# DUE_shield.net
KiCad netlist of a schematic drawn in EAGLE
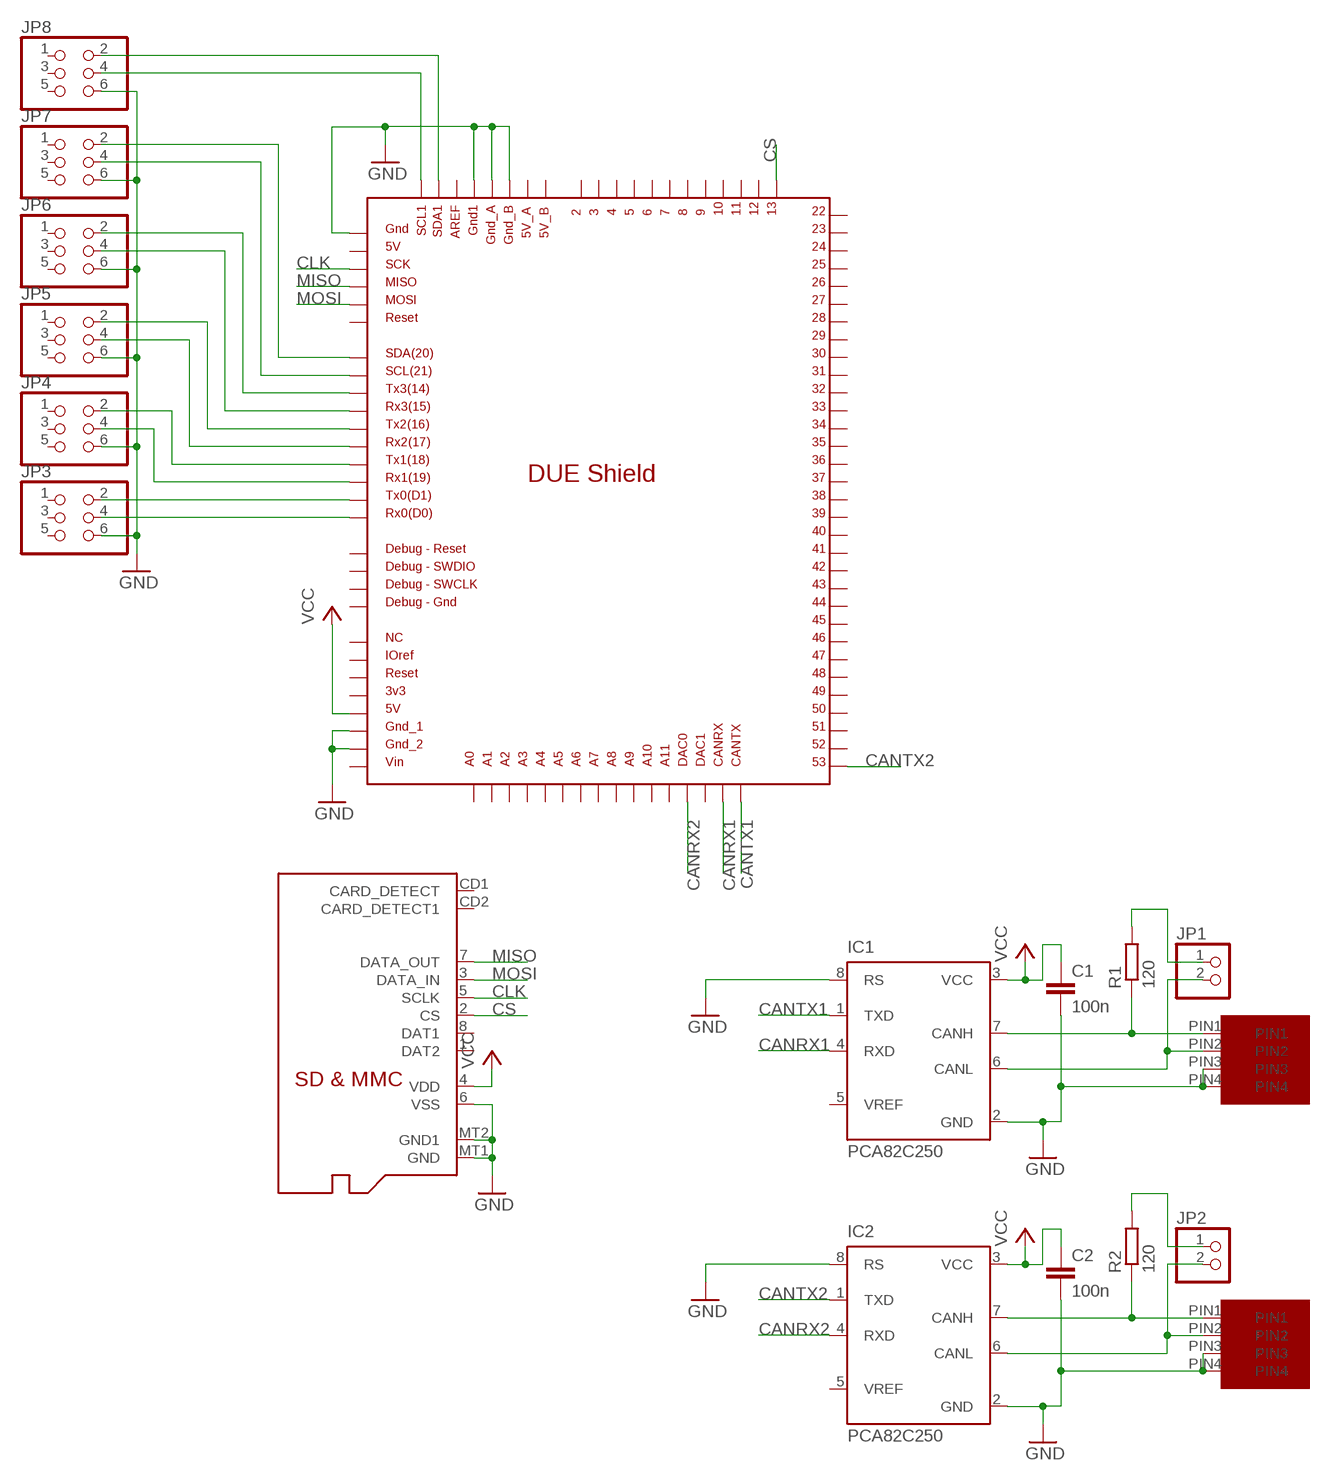
[diagram p0: schematic, sheet 1]

(export (version "E")
  (design (tool "Eeschema 10.0.6"))
  (components
    (comp (ref "C1")
      (value "100n")
      (footprint "eagle-import:C050-024X044")
      (libsource (lib "eagle-import") (part "C-EU050-024X044"))
    )
    (comp (ref "C2")
      (value "100n")
      (footprint "eagle-import:C050-024X044")
      (libsource (lib "eagle-import") (part "C-EU050-024X044"))
    )
    (comp (ref "IC1")
      (value "PCA82C250")
      (footprint "eagle-import:DIL08")
      (libsource (lib "eagle-import") (part "PCA82C250"))
    )
    (comp (ref "IC2")
      (value "PCA82C250")
      (footprint "eagle-import:DIL08")
      (libsource (lib "eagle-import") (part "PCA82C250"))
    )
    (comp (ref "JP1")
      (value "PINHD-1X2")
      (footprint "eagle-import:1X02")
      (libsource (lib "eagle-import") (part "PINHD-1X2"))
    )
    (comp (ref "JP2")
      (value "PINHD-1X2")
      (footprint "eagle-import:1X02")
      (libsource (lib "eagle-import") (part "PINHD-1X2"))
    )
    (comp (ref "JP3")
      (value "PINHD-2X3")
      (footprint "eagle-import:2X03")
      (libsource (lib "eagle-import") (part "PINHD-2X3"))
    )
    (comp (ref "JP4")
      (value "PINHD-2X3")
      (footprint "eagle-import:2X03")
      (libsource (lib "eagle-import") (part "PINHD-2X3"))
    )
    (comp (ref "JP5")
      (value "PINHD-2X3")
      (footprint "eagle-import:2X03")
      (libsource (lib "eagle-import") (part "PINHD-2X3"))
    )
    (comp (ref "JP6")
      (value "PINHD-2X3")
      (footprint "eagle-import:2X03")
      (libsource (lib "eagle-import") (part "PINHD-2X3"))
    )
    (comp (ref "JP7")
      (value "PINHD-2X3")
      (footprint "eagle-import:2X03")
      (libsource (lib "eagle-import") (part "PINHD-2X3"))
    )
    (comp (ref "JP8")
      (value "PINHD-2X3")
      (footprint "eagle-import:2X03")
      (libsource (lib "eagle-import") (part "PINHD-2X3"))
    )
    (comp (ref "R1")
      (value "120")
      (footprint "eagle-import:0204_7")
      (libsource (lib "eagle-import") (part "R-EU_0204/7"))
    )
    (comp (ref "R2")
      (value "120")
      (footprint "eagle-import:0204_7")
      (libsource (lib "eagle-import") (part "R-EU_0204/7"))
    )
    (comp (ref "U$1")
      (value "DUE(NORMAL)")
      (footprint "eagle-import:DUE(NORMAL)")
      (libsource (lib "eagle-import") (part "DUE(NORMAL)"))
    )
    (comp (ref "U$2")
      (value "MICROFIT4")
      (footprint "eagle-import:MICROFIT4SOCK")
      (libsource (lib "eagle-import") (part "MICROFIT4"))
    )
    (comp (ref "U$3")
      (value "MICROFIT4")
      (footprint "eagle-import:MICROFIT4SOCK")
      (libsource (lib "eagle-import") (part "MICROFIT4"))
    )
    (comp (ref "U$4")
      (value "MICROSD")
      (footprint "eagle-import:MICROSD")
      (libsource (lib "eagle-import") (part "MICROSD"))
    )
  )
  (nets
    (net (code "1") (name "/CANRX1") (class "Default")
      (node (ref "IC1") (pin "4") (pinfunction "RXD_4") (pintype "output"))
      (node (ref "U$1") (pin "CANRX") (pinfunction "CANRX_CANRX") (pintype "bidirectional"))
    )
    (net (code "2") (name "/CANRX2") (class "Default")
      (node (ref "IC2") (pin "4") (pinfunction "RXD_4") (pintype "output"))
      (node (ref "U$1") (pin "DAC0") (pinfunction "DAC0_DAC0") (pintype "bidirectional"))
    )
    (net (code "3") (name "/CANTX1") (class "Default")
      (node (ref "IC1") (pin "1") (pinfunction "TXD_1") (pintype "input"))
      (node (ref "U$1") (pin "CANTX") (pinfunction "CANTX_CANTX") (pintype "bidirectional"))
    )
    (net (code "4") (name "/CANTX2") (class "Default")
      (node (ref "IC2") (pin "1") (pinfunction "TXD_1") (pintype "input"))
      (node (ref "U$1") (pin "53") (pinfunction "53_53") (pintype "bidirectional"))
    )
    (net (code "5") (name "/CLK") (class "Default")
      (node (ref "U$1") (pin "SCK_ICSP") (pinfunction "SCK_ICSP_SCK_ICSP") (pintype "bidirectional"))
      (node (ref "U$4") (pin "5") (pinfunction "SCLK_5") (pintype "input"))
    )
    (net (code "6") (name "/CS") (class "Default")
      (node (ref "U$1") (pin "13") (pinfunction "13_13") (pintype "bidirectional"))
      (node (ref "U$4") (pin "2") (pinfunction "CS_2") (pintype "input"))
    )
    (net (code "7") (name "/MISO") (class "Default")
      (node (ref "U$1") (pin "MISO_ICSP") (pinfunction "MISO_ICSP_MISO_ICSP") (pintype "bidirectional"))
      (node (ref "U$4") (pin "7") (pinfunction "DATA_OUT_7") (pintype "output"))
    )
    (net (code "8") (name "/MOSI") (class "Default")
      (node (ref "U$1") (pin "MOSI_ICSP") (pinfunction "MOSI_ICSP_MOSI_ICSP") (pintype "bidirectional"))
      (node (ref "U$4") (pin "3") (pinfunction "DATA_IN_3") (pintype "input"))
    )
    (net (code "9") (name "GND") (class "Default")
      (node (ref "C1") (pin "2") (pinfunction "2_2") (pintype "passive"))
      (node (ref "C2") (pin "2") (pinfunction "2_2") (pintype "passive"))
      (node (ref "IC1") (pin "2") (pinfunction "GND_2") (pintype "power_in"))
      (node (ref "IC1") (pin "8") (pinfunction "RS_8") (pintype "input"))
      (node (ref "IC2") (pin "2") (pinfunction "GND_2") (pintype "power_in"))
      (node (ref "IC2") (pin "8") (pinfunction "RS_8") (pintype "input"))
      (node (ref "JP3") (pin "6") (pinfunction "6_6") (pintype "passive"))
      (node (ref "JP4") (pin "6") (pinfunction "6_6") (pintype "passive"))
      (node (ref "JP5") (pin "6") (pinfunction "6_6") (pintype "passive"))
      (node (ref "JP6") (pin "6") (pinfunction "6_6") (pintype "passive"))
      (node (ref "JP7") (pin "6") (pinfunction "6_6") (pintype "passive"))
      (node (ref "JP8") (pin "6") (pinfunction "6_6") (pintype "passive"))
      (node (ref "U$1") (pin "5V_ICSP") (pinfunction "5V_ICSP_5V_ICSP") (pintype "bidirectional"))
      (node (ref "U$1") (pin "GND1") (pinfunction "GND1_GND1") (pintype "bidirectional"))
      (node (ref "U$1") (pin "GND_1") (pinfunction "GND_1_GND_1") (pintype "bidirectional"))
      (node (ref "U$1") (pin "GND_2") (pinfunction "GND_2_GND_2") (pintype "bidirectional"))
      (node (ref "U$1") (pin "GND_A") (pinfunction "GND_A_GND_A") (pintype "bidirectional"))
      (node (ref "U$1") (pin "GND_B") (pinfunction "GND_B_GND_B") (pintype "bidirectional"))
      (node (ref "U$2") (pin "PIN3") (pinfunction "PIN3_PIN3") (pintype "bidirectional"))
      (node (ref "U$2") (pin "PIN4") (pinfunction "PIN4_PIN4") (pintype "bidirectional"))
      (node (ref "U$3") (pin "PIN3") (pinfunction "PIN3_PIN3") (pintype "bidirectional"))
      (node (ref "U$3") (pin "PIN4") (pinfunction "PIN4_PIN4") (pintype "bidirectional"))
      (node (ref "U$4") (pin "6") (pinfunction "VSS_6") (pintype "power_in"))
      (node (ref "U$4") (pin "MT1") (pinfunction "GND_MT1") (pintype "power_in"))
      (node (ref "U$4") (pin "MT2") (pinfunction "GND1_MT2") (pintype "power_in"))
    )
    (net (code "10") (name "Net-(IC1-CANH)") (class "Default")
      (node (ref "IC1") (pin "7") (pinfunction "CANH_7") (pintype "bidirectional"))
      (node (ref "R1") (pin "1") (pinfunction "1_1") (pintype "passive"))
      (node (ref "U$2") (pin "PIN1") (pinfunction "PIN1_PIN1") (pintype "bidirectional"))
    )
    (net (code "11") (name "Net-(IC1-CANL)") (class "Default")
      (node (ref "IC1") (pin "6") (pinfunction "CANL_6") (pintype "bidirectional"))
      (node (ref "JP1") (pin "2") (pinfunction "2_2") (pintype "passive"))
      (node (ref "U$2") (pin "PIN2") (pinfunction "PIN2_PIN2") (pintype "bidirectional"))
    )
    (net (code "12") (name "Net-(IC2-CANH)") (class "Default")
      (node (ref "IC2") (pin "7") (pinfunction "CANH_7") (pintype "bidirectional"))
      (node (ref "R2") (pin "1") (pinfunction "1_1") (pintype "passive"))
      (node (ref "U$3") (pin "PIN1") (pinfunction "PIN1_PIN1") (pintype "bidirectional"))
    )
    (net (code "13") (name "Net-(IC2-CANL)") (class "Default")
      (node (ref "IC2") (pin "6") (pinfunction "CANL_6") (pintype "bidirectional"))
      (node (ref "JP2") (pin "2") (pinfunction "2_2") (pintype "passive"))
      (node (ref "U$3") (pin "PIN2") (pinfunction "PIN2_PIN2") (pintype "bidirectional"))
    )
    (net (code "14") (name "Net-(JP1-Pad1)") (class "Default")
      (node (ref "JP1") (pin "1") (pinfunction "1_1") (pintype "passive"))
      (node (ref "R1") (pin "2") (pinfunction "2_2") (pintype "passive"))
    )
    (net (code "15") (name "Net-(JP2-Pad1)") (class "Default")
      (node (ref "JP2") (pin "1") (pinfunction "1_1") (pintype "passive"))
      (node (ref "R2") (pin "2") (pinfunction "2_2") (pintype "passive"))
    )
    (net (code "16") (name "Net-(JP3-Pad2)") (class "Default")
      (node (ref "JP3") (pin "2") (pinfunction "2_2") (pintype "passive"))
      (node (ref "U$1") (pin "TX0") (pinfunction "TX0_TX0") (pintype "bidirectional"))
    )
    (net (code "17") (name "Net-(JP3-Pad4)") (class "Default")
      (node (ref "JP3") (pin "4") (pinfunction "4_4") (pintype "passive"))
      (node (ref "U$1") (pin "RX0") (pinfunction "RX0_RX0") (pintype "bidirectional"))
    )
    (net (code "18") (name "Net-(JP4-Pad2)") (class "Default")
      (node (ref "JP4") (pin "2") (pinfunction "2_2") (pintype "passive"))
      (node (ref "U$1") (pin "TX1") (pinfunction "TX1_TX1") (pintype "bidirectional"))
    )
    (net (code "19") (name "Net-(JP4-Pad4)") (class "Default")
      (node (ref "JP4") (pin "4") (pinfunction "4_4") (pintype "passive"))
      (node (ref "U$1") (pin "RX1") (pinfunction "RX1_RX1") (pintype "bidirectional"))
    )
    (net (code "20") (name "Net-(JP5-Pad2)") (class "Default")
      (node (ref "JP5") (pin "2") (pinfunction "2_2") (pintype "passive"))
      (node (ref "U$1") (pin "TX2") (pinfunction "TX2_TX2") (pintype "bidirectional"))
    )
    (net (code "21") (name "Net-(JP5-Pad4)") (class "Default")
      (node (ref "JP5") (pin "4") (pinfunction "4_4") (pintype "passive"))
      (node (ref "U$1") (pin "RX2") (pinfunction "RX2_RX2") (pintype "bidirectional"))
    )
    (net (code "22") (name "Net-(JP6-Pad2)") (class "Default")
      (node (ref "JP6") (pin "2") (pinfunction "2_2") (pintype "passive"))
      (node (ref "U$1") (pin "TX3") (pinfunction "TX3_TX3") (pintype "bidirectional"))
    )
    (net (code "23") (name "Net-(JP6-Pad4)") (class "Default")
      (node (ref "JP6") (pin "4") (pinfunction "4_4") (pintype "passive"))
      (node (ref "U$1") (pin "RX3") (pinfunction "RX3_RX3") (pintype "bidirectional"))
    )
    (net (code "24") (name "Net-(JP7-Pad2)") (class "Default")
      (node (ref "JP7") (pin "2") (pinfunction "2_2") (pintype "passive"))
      (node (ref "U$1") (pin "SDA") (pinfunction "SDA_SDA") (pintype "bidirectional"))
    )
    (net (code "25") (name "Net-(JP7-Pad4)") (class "Default")
      (node (ref "JP7") (pin "4") (pinfunction "4_4") (pintype "passive"))
      (node (ref "U$1") (pin "SCL") (pinfunction "SCL_SCL") (pintype "bidirectional"))
    )
    (net (code "26") (name "Net-(JP8-Pad2)") (class "Default")
      (node (ref "JP8") (pin "2") (pinfunction "2_2") (pintype "passive"))
      (node (ref "U$1") (pin "SDA1") (pinfunction "SDA1_SDA1") (pintype "bidirectional"))
    )
    (net (code "27") (name "Net-(JP8-Pad4)") (class "Default")
      (node (ref "JP8") (pin "4") (pinfunction "4_4") (pintype "passive"))
      (node (ref "U$1") (pin "SCL1") (pinfunction "SCL1_SCL1") (pintype "bidirectional"))
    )
    (net (code "28") (name "VCC") (class "Default")
      (node (ref "C1") (pin "1") (pinfunction "1_1") (pintype "passive"))
      (node (ref "C2") (pin "1") (pinfunction "1_1") (pintype "passive"))
      (node (ref "IC1") (pin "3") (pinfunction "VCC_3") (pintype "power_in"))
      (node (ref "IC2") (pin "3") (pinfunction "VCC_3") (pintype "power_in"))
      (node (ref "U$1") (pin "5V") (pinfunction "5V_5V") (pintype "bidirectional"))
      (node (ref "U$4") (pin "4") (pinfunction "VDD_4") (pintype "power_in"))
    )
    (net (code "29") (name "unconnected-(IC1-VREF-Pad5)") (class "Default")
      (node (ref "IC1") (pin "5") (pinfunction "VREF_5") (pintype "output"))
    )
    (net (code "30") (name "unconnected-(IC2-VREF-Pad5)") (class "Default")
      (node (ref "IC2") (pin "5") (pinfunction "VREF_5") (pintype "output"))
    )
    (net (code "31") (name "unconnected-(JP3-Pad1)") (class "Default")
      (node (ref "JP3") (pin "1") (pinfunction "1_1") (pintype "passive"))
    )
    (net (code "32") (name "unconnected-(JP3-Pad3)") (class "Default")
      (node (ref "JP3") (pin "3") (pinfunction "3_3") (pintype "passive"))
    )
    (net (code "33") (name "unconnected-(JP3-Pad5)") (class "Default")
      (node (ref "JP3") (pin "5") (pinfunction "5_5") (pintype "passive"))
    )
    (net (code "34") (name "unconnected-(JP4-Pad1)") (class "Default")
      (node (ref "JP4") (pin "1") (pinfunction "1_1") (pintype "passive"))
    )
    (net (code "35") (name "unconnected-(JP4-Pad3)") (class "Default")
      (node (ref "JP4") (pin "3") (pinfunction "3_3") (pintype "passive"))
    )
    (net (code "36") (name "unconnected-(JP4-Pad5)") (class "Default")
      (node (ref "JP4") (pin "5") (pinfunction "5_5") (pintype "passive"))
    )
    (net (code "37") (name "unconnected-(JP5-Pad1)") (class "Default")
      (node (ref "JP5") (pin "1") (pinfunction "1_1") (pintype "passive"))
    )
    (net (code "38") (name "unconnected-(JP5-Pad3)") (class "Default")
      (node (ref "JP5") (pin "3") (pinfunction "3_3") (pintype "passive"))
    )
    (net (code "39") (name "unconnected-(JP5-Pad5)") (class "Default")
      (node (ref "JP5") (pin "5") (pinfunction "5_5") (pintype "passive"))
    )
    (net (code "40") (name "unconnected-(JP6-Pad1)") (class "Default")
      (node (ref "JP6") (pin "1") (pinfunction "1_1") (pintype "passive"))
    )
    (net (code "41") (name "unconnected-(JP6-Pad3)") (class "Default")
      (node (ref "JP6") (pin "3") (pinfunction "3_3") (pintype "passive"))
    )
    (net (code "42") (name "unconnected-(JP6-Pad5)") (class "Default")
      (node (ref "JP6") (pin "5") (pinfunction "5_5") (pintype "passive"))
    )
    (net (code "43") (name "unconnected-(JP7-Pad1)") (class "Default")
      (node (ref "JP7") (pin "1") (pinfunction "1_1") (pintype "passive"))
    )
    (net (code "44") (name "unconnected-(JP7-Pad3)") (class "Default")
      (node (ref "JP7") (pin "3") (pinfunction "3_3") (pintype "passive"))
    )
    (net (code "45") (name "unconnected-(JP7-Pad5)") (class "Default")
      (node (ref "JP7") (pin "5") (pinfunction "5_5") (pintype "passive"))
    )
    (net (code "46") (name "unconnected-(JP8-Pad1)") (class "Default")
      (node (ref "JP8") (pin "1") (pinfunction "1_1") (pintype "passive"))
    )
    (net (code "47") (name "unconnected-(JP8-Pad3)") (class "Default")
      (node (ref "JP8") (pin "3") (pinfunction "3_3") (pintype "passive"))
    )
    (net (code "48") (name "unconnected-(JP8-Pad5)") (class "Default")
      (node (ref "JP8") (pin "5") (pinfunction "5_5") (pintype "passive"))
    )
    (net (code "49") (name "unconnected-(U$1-Pad2)") (class "Default")
      (node (ref "U$1") (pin "2") (pinfunction "2_2") (pintype "bidirectional"))
    )
    (net (code "50") (name "unconnected-(U$1-Pad3)") (class "Default")
      (node (ref "U$1") (pin "3") (pinfunction "3_3") (pintype "bidirectional"))
    )
    (net (code "51") (name "unconnected-(U$1-Pad3V3)") (class "Default")
      (node (ref "U$1") (pin "3V3") (pinfunction "3V3_3V3") (pintype "bidirectional"))
    )
    (net (code "52") (name "unconnected-(U$1-Pad4)") (class "Default")
      (node (ref "U$1") (pin "4") (pinfunction "4_4") (pintype "bidirectional"))
    )
    (net (code "53") (name "unconnected-(U$1-Pad5)") (class "Default")
      (node (ref "U$1") (pin "5") (pinfunction "5_5") (pintype "bidirectional"))
    )
    (net (code "54") (name "unconnected-(U$1-Pad5V_A)") (class "Default")
      (node (ref "U$1") (pin "5V_A") (pinfunction "5V_A_5V_A") (pintype "bidirectional"))
    )
    (net (code "55") (name "unconnected-(U$1-Pad5V_B)") (class "Default")
      (node (ref "U$1") (pin "5V_B") (pinfunction "5V_B_5V_B") (pintype "bidirectional"))
    )
    (net (code "56") (name "unconnected-(U$1-Pad6)") (class "Default")
      (node (ref "U$1") (pin "6") (pinfunction "6_6") (pintype "bidirectional"))
    )
    (net (code "57") (name "unconnected-(U$1-Pad7)") (class "Default")
      (node (ref "U$1") (pin "7") (pinfunction "7_7") (pintype "bidirectional"))
    )
    (net (code "58") (name "unconnected-(U$1-Pad8)") (class "Default")
      (node (ref "U$1") (pin "8") (pinfunction "8_8") (pintype "bidirectional"))
    )
    (net (code "59") (name "unconnected-(U$1-Pad9)") (class "Default")
      (node (ref "U$1") (pin "9") (pinfunction "9_9") (pintype "bidirectional"))
    )
    (net (code "60") (name "unconnected-(U$1-Pad10)") (class "Default")
      (node (ref "U$1") (pin "10") (pinfunction "10_10") (pintype "bidirectional"))
    )
    (net (code "61") (name "unconnected-(U$1-Pad11)") (class "Default")
      (node (ref "U$1") (pin "11") (pinfunction "11_11") (pintype "bidirectional"))
    )
    (net (code "62") (name "unconnected-(U$1-Pad12)") (class "Default")
      (node (ref "U$1") (pin "12") (pinfunction "12_12") (pintype "bidirectional"))
    )
    (net (code "63") (name "unconnected-(U$1-Pad22)") (class "Default")
      (node (ref "U$1") (pin "22") (pinfunction "22_22") (pintype "bidirectional"))
    )
    (net (code "64") (name "unconnected-(U$1-Pad23)") (class "Default")
      (node (ref "U$1") (pin "23") (pinfunction "23_23") (pintype "bidirectional"))
    )
    (net (code "65") (name "unconnected-(U$1-Pad24)") (class "Default")
      (node (ref "U$1") (pin "24") (pinfunction "24_24") (pintype "bidirectional"))
    )
    (net (code "66") (name "unconnected-(U$1-Pad25)") (class "Default")
      (node (ref "U$1") (pin "25") (pinfunction "25_25") (pintype "bidirectional"))
    )
    (net (code "67") (name "unconnected-(U$1-Pad26)") (class "Default")
      (node (ref "U$1") (pin "26") (pinfunction "26_26") (pintype "bidirectional"))
    )
    (net (code "68") (name "unconnected-(U$1-Pad27)") (class "Default")
      (node (ref "U$1") (pin "27") (pinfunction "27_27") (pintype "bidirectional"))
    )
    (net (code "69") (name "unconnected-(U$1-Pad28)") (class "Default")
      (node (ref "U$1") (pin "28") (pinfunction "28_28") (pintype "bidirectional"))
    )
    (net (code "70") (name "unconnected-(U$1-Pad29)") (class "Default")
      (node (ref "U$1") (pin "29") (pinfunction "29_29") (pintype "bidirectional"))
    )
    (net (code "71") (name "unconnected-(U$1-Pad30)") (class "Default")
      (node (ref "U$1") (pin "30") (pinfunction "30_30") (pintype "bidirectional"))
    )
    (net (code "72") (name "unconnected-(U$1-Pad31)") (class "Default")
      (node (ref "U$1") (pin "31") (pinfunction "31_31") (pintype "bidirectional"))
    )
    (net (code "73") (name "unconnected-(U$1-Pad32)") (class "Default")
      (node (ref "U$1") (pin "32") (pinfunction "32_32") (pintype "bidirectional"))
    )
    (net (code "74") (name "unconnected-(U$1-Pad33)") (class "Default")
      (node (ref "U$1") (pin "33") (pinfunction "33_33") (pintype "bidirectional"))
    )
    (net (code "75") (name "unconnected-(U$1-Pad34)") (class "Default")
      (node (ref "U$1") (pin "34") (pinfunction "34_34") (pintype "bidirectional"))
    )
    (net (code "76") (name "unconnected-(U$1-Pad35)") (class "Default")
      (node (ref "U$1") (pin "35") (pinfunction "35_35") (pintype "bidirectional"))
    )
    (net (code "77") (name "unconnected-(U$1-Pad36)") (class "Default")
      (node (ref "U$1") (pin "36") (pinfunction "36_36") (pintype "bidirectional"))
    )
    (net (code "78") (name "unconnected-(U$1-Pad37)") (class "Default")
      (node (ref "U$1") (pin "37") (pinfunction "37_37") (pintype "bidirectional"))
    )
    (net (code "79") (name "unconnected-(U$1-Pad38)") (class "Default")
      (node (ref "U$1") (pin "38") (pinfunction "38_38") (pintype "bidirectional"))
    )
    (net (code "80") (name "unconnected-(U$1-Pad39)") (class "Default")
      (node (ref "U$1") (pin "39") (pinfunction "39_39") (pintype "bidirectional"))
    )
    (net (code "81") (name "unconnected-(U$1-Pad40)") (class "Default")
      (node (ref "U$1") (pin "40") (pinfunction "40_40") (pintype "bidirectional"))
    )
    (net (code "82") (name "unconnected-(U$1-Pad41)") (class "Default")
      (node (ref "U$1") (pin "41") (pinfunction "41_41") (pintype "bidirectional"))
    )
    (net (code "83") (name "unconnected-(U$1-Pad42)") (class "Default")
      (node (ref "U$1") (pin "42") (pinfunction "42_42") (pintype "bidirectional"))
    )
    (net (code "84") (name "unconnected-(U$1-Pad43)") (class "Default")
      (node (ref "U$1") (pin "43") (pinfunction "43_43") (pintype "bidirectional"))
    )
    (net (code "85") (name "unconnected-(U$1-Pad44)") (class "Default")
      (node (ref "U$1") (pin "44") (pinfunction "44_44") (pintype "bidirectional"))
    )
    (net (code "86") (name "unconnected-(U$1-Pad45)") (class "Default")
      (node (ref "U$1") (pin "45") (pinfunction "45_45") (pintype "bidirectional"))
    )
    (net (code "87") (name "unconnected-(U$1-Pad46)") (class "Default")
      (node (ref "U$1") (pin "46") (pinfunction "46_46") (pintype "bidirectional"))
    )
    (net (code "88") (name "unconnected-(U$1-Pad47)") (class "Default")
      (node (ref "U$1") (pin "47") (pinfunction "47_47") (pintype "bidirectional"))
    )
    (net (code "89") (name "unconnected-(U$1-Pad48)") (class "Default")
      (node (ref "U$1") (pin "48") (pinfunction "48_48") (pintype "bidirectional"))
    )
    (net (code "90") (name "unconnected-(U$1-Pad49)") (class "Default")
      (node (ref "U$1") (pin "49") (pinfunction "49_49") (pintype "bidirectional"))
    )
    (net (code "91") (name "unconnected-(U$1-Pad50)") (class "Default")
      (node (ref "U$1") (pin "50") (pinfunction "50_50") (pintype "bidirectional"))
    )
    (net (code "92") (name "unconnected-(U$1-Pad51)") (class "Default")
      (node (ref "U$1") (pin "51") (pinfunction "51_51") (pintype "bidirectional"))
    )
    (net (code "93") (name "unconnected-(U$1-Pad52)") (class "Default")
      (node (ref "U$1") (pin "52") (pinfunction "52_52") (pintype "bidirectional"))
    )
    (net (code "94") (name "unconnected-(U$1-PadA0)") (class "Default")
      (node (ref "U$1") (pin "A0") (pinfunction "A0_A0") (pintype "bidirectional"))
    )
    (net (code "95") (name "unconnected-(U$1-PadA1)") (class "Default")
      (node (ref "U$1") (pin "A1") (pinfunction "A1_A1") (pintype "bidirectional"))
    )
    (net (code "96") (name "unconnected-(U$1-PadA2)") (class "Default")
      (node (ref "U$1") (pin "A2") (pinfunction "A2_A2") (pintype "bidirectional"))
    )
    (net (code "97") (name "unconnected-(U$1-PadA3)") (class "Default")
      (node (ref "U$1") (pin "A3") (pinfunction "A3_A3") (pintype "bidirectional"))
    )
    (net (code "98") (name "unconnected-(U$1-PadA4)") (class "Default")
      (node (ref "U$1") (pin "A4") (pinfunction "A4_A4") (pintype "bidirectional"))
    )
    (net (code "99") (name "unconnected-(U$1-PadA5)") (class "Default")
      (node (ref "U$1") (pin "A5") (pinfunction "A5_A5") (pintype "bidirectional"))
    )
    (net (code "100") (name "unconnected-(U$1-PadA6)") (class "Default")
      (node (ref "U$1") (pin "A6") (pinfunction "A6_A6") (pintype "bidirectional"))
    )
    (net (code "101") (name "unconnected-(U$1-PadA7)") (class "Default")
      (node (ref "U$1") (pin "A7") (pinfunction "A7_A7") (pintype "bidirectional"))
    )
    (net (code "102") (name "unconnected-(U$1-PadA8)") (class "Default")
      (node (ref "U$1") (pin "A8") (pinfunction "A8_A8") (pintype "bidirectional"))
    )
    (net (code "103") (name "unconnected-(U$1-PadA9)") (class "Default")
      (node (ref "U$1") (pin "A9") (pinfunction "A9_A9") (pintype "bidirectional"))
    )
    (net (code "104") (name "unconnected-(U$1-PadA10)") (class "Default")
      (node (ref "U$1") (pin "A10") (pinfunction "A10_A10") (pintype "bidirectional"))
    )
    (net (code "105") (name "unconnected-(U$1-PadA11)") (class "Default")
      (node (ref "U$1") (pin "A11") (pinfunction "A11_A11") (pintype "bidirectional"))
    )
    (net (code "106") (name "unconnected-(U$1-PadAREF)") (class "Default")
      (node (ref "U$1") (pin "AREF") (pinfunction "AREF_AREF") (pintype "bidirectional"))
    )
    (net (code "107") (name "unconnected-(U$1-PadDAC1)") (class "Default")
      (node (ref "U$1") (pin "DAC1") (pinfunction "DAC1_DAC1") (pintype "bidirectional"))
    )
    (net (code "108") (name "unconnected-(U$1-PadGND_DEBUG)") (class "Default")
      (node (ref "U$1") (pin "GND_DEBUG") (pinfunction "GND_DEBUG_GND_DEBUG") (pintype "bidirectional"))
    )
    (net (code "109") (name "unconnected-(U$1-PadGND_ICSP)") (class "Default")
      (node (ref "U$1") (pin "GND_ICSP") (pinfunction "GND_ICSP_GND_ICSP") (pintype "bidirectional"))
    )
    (net (code "110") (name "unconnected-(U$1-PadIOREF)") (class "Default")
      (node (ref "U$1") (pin "IOREF") (pinfunction "IOREF_IOREF") (pintype "bidirectional"))
    )
    (net (code "111") (name "unconnected-(U$1-PadNC)") (class "Default")
      (node (ref "U$1") (pin "NC") (pinfunction "NC_NC") (pintype "bidirectional"))
    )
    (net (code "112") (name "unconnected-(U$1-PadRESET)") (class "Default")
      (node (ref "U$1") (pin "RESET") (pinfunction "RESET_RESET") (pintype "bidirectional"))
    )
    (net (code "113") (name "unconnected-(U$1-PadRESET_DEBUG)") (class "Default")
      (node (ref "U$1") (pin "RESET_DEBUG") (pinfunction "RESET_DEBUG_RESET_DEBUG") (pintype "bidirectional"))
    )
    (net (code "114") (name "unconnected-(U$1-PadRESET_ICSP)") (class "Default")
      (node (ref "U$1") (pin "RESET_ICSP") (pinfunction "RESET_ICSP_RESET_ICSP") (pintype "bidirectional"))
    )
    (net (code "115") (name "unconnected-(U$1-PadSWCLK_DEBUG)") (class "Default")
      (node (ref "U$1") (pin "SWCLK_DEBUG") (pinfunction "SWCLK_DEBUG_SWCLK_DEBUG") (pintype "bidirectional"))
    )
    (net (code "116") (name "unconnected-(U$1-PadSWDIO_DEBUG)") (class "Default")
      (node (ref "U$1") (pin "SWDIO_DEBUG") (pinfunction "SWDIO_DEBUG_SWDIO_DEBUG") (pintype "bidirectional"))
    )
    (net (code "117") (name "unconnected-(U$1-PadVIN)") (class "Default")
      (node (ref "U$1") (pin "VIN") (pinfunction "VIN_VIN") (pintype "bidirectional"))
    )
    (net (code "118") (name "unconnected-(U$4-CARD_DETECT-PadCD1)") (class "Default")
      (node (ref "U$4") (pin "CD1") (pinfunction "CARD_DETECT_CD1") (pintype "passive"))
    )
    (net (code "119") (name "unconnected-(U$4-CARD_DETECT1-PadCD2)") (class "Default")
      (node (ref "U$4") (pin "CD2") (pinfunction "CARD_DETECT1_CD2") (pintype "passive"))
    )
    (net (code "120") (name "unconnected-(U$4-DAT1-Pad8)") (class "Default")
      (node (ref "U$4") (pin "8") (pinfunction "DAT1_8") (pintype "bidirectional"))
    )
    (net (code "121") (name "unconnected-(U$4-DAT2-Pad1)") (class "Default")
      (node (ref "U$4") (pin "1") (pinfunction "DAT2_1") (pintype "bidirectional"))
    )
  )
)
